# Power_Distribution.net
KiCad netlist of a schematic drawn in EAGLE
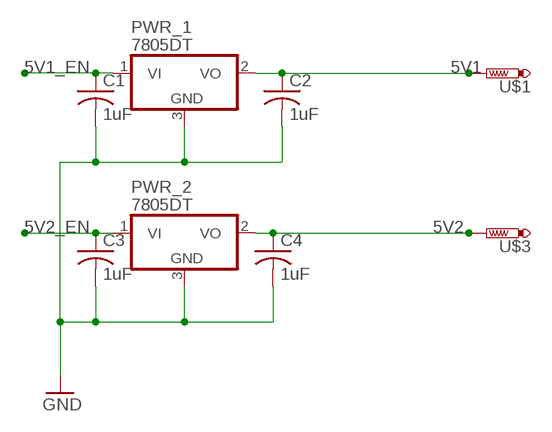
[diagram p0: schematic, sheet 1]
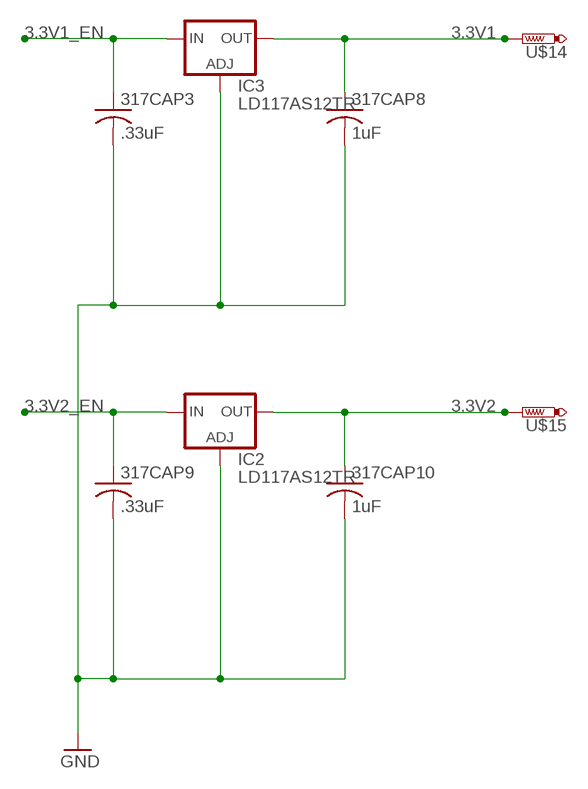
[diagram p1: schematic, sheet 2]
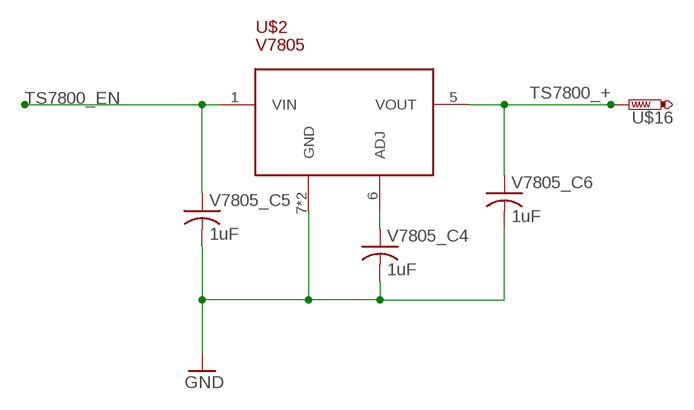
[diagram p2: schematic, sheet 3]
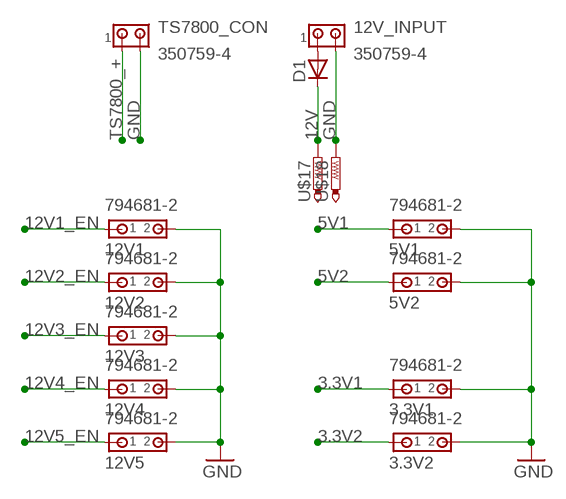
[diagram p3: schematic, sheet 4]
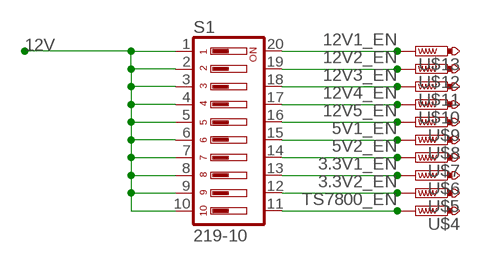
[diagram p4: schematic, sheet 5]

(export (version "E")
  (design (tool "Eeschema 10.0.6"))
  (components
    (comp (ref "S1")
      (value "219-10")
      (footprint "eagle-import:CTS-219-10")
      (fields (field (name "MF") "SLI (CML/IDI)") (field (name "MPN") "219-10PK"))
      (libsource (lib "eagle-import") (part "219-10"))
    )
    (comp (ref "U$4")
      (value "TESTPAD-20MIL")
      (footprint "eagle-import:20MIL")
      (libsource (lib "eagle-import") (part "TESTPAD-20MIL"))
    )
    (comp (ref "U$5")
      (value "TESTPAD-20MIL")
      (footprint "eagle-import:20MIL")
      (libsource (lib "eagle-import") (part "TESTPAD-20MIL"))
    )
    (comp (ref "U$6")
      (value "TESTPAD-20MIL")
      (footprint "eagle-import:20MIL")
      (libsource (lib "eagle-import") (part "TESTPAD-20MIL"))
    )
    (comp (ref "U$7")
      (value "TESTPAD-20MIL")
      (footprint "eagle-import:20MIL")
      (libsource (lib "eagle-import") (part "TESTPAD-20MIL"))
    )
    (comp (ref "U$8")
      (value "TESTPAD-20MIL")
      (footprint "eagle-import:20MIL")
      (libsource (lib "eagle-import") (part "TESTPAD-20MIL"))
    )
    (comp (ref "U$9")
      (value "TESTPAD-20MIL")
      (footprint "eagle-import:20MIL")
      (libsource (lib "eagle-import") (part "TESTPAD-20MIL"))
    )
    (comp (ref "U$10")
      (value "TESTPAD-20MIL")
      (footprint "eagle-import:20MIL")
      (libsource (lib "eagle-import") (part "TESTPAD-20MIL"))
    )
    (comp (ref "U$11")
      (value "TESTPAD-20MIL")
      (footprint "eagle-import:20MIL")
      (libsource (lib "eagle-import") (part "TESTPAD-20MIL"))
    )
    (comp (ref "U$12")
      (value "TESTPAD-20MIL")
      (footprint "eagle-import:20MIL")
      (libsource (lib "eagle-import") (part "TESTPAD-20MIL"))
    )
    (comp (ref "U$13")
      (value "TESTPAD-20MIL")
      (footprint "eagle-import:20MIL")
      (libsource (lib "eagle-import") (part "TESTPAD-20MIL"))
    )
    (comp (ref "U$2")
      (value "V7805")
      (footprint "eagle-import:V7805")
      (libsource (lib "eagle-import") (part "V7805"))
    )
    (comp (ref "U$16")
      (value "TESTPAD-20MIL")
      (footprint "eagle-import:20MIL")
      (libsource (lib "eagle-import") (part "TESTPAD-20MIL"))
    )
    (comp (ref "V7805_C4")
      (value "1uF")
      (footprint "eagle-import:C1206")
      (libsource (lib "eagle-import") (part "C-USC1206"))
    )
    (comp (ref "V7805_C5")
      (value "1uF")
      (footprint "eagle-import:C1206")
      (libsource (lib "eagle-import") (part "C-USC1206"))
    )
    (comp (ref "V7805_C6")
      (value "1uF")
      (footprint "eagle-import:C1206")
      (libsource (lib "eagle-import") (part "C-USC1206"))
    )
    (comp (ref "3.3V1")
      (value "794681-2")
      (footprint "eagle-import:794681-2")
      (libsource (lib "eagle-import") (part "794681-2"))
    )
    (comp (ref "3.3V2")
      (value "794681-2")
      (footprint "eagle-import:794681-2")
      (libsource (lib "eagle-import") (part "794681-2"))
    )
    (comp (ref "5V1")
      (value "794681-2")
      (footprint "eagle-import:794681-2")
      (libsource (lib "eagle-import") (part "794681-2"))
    )
    (comp (ref "5V2")
      (value "794681-2")
      (footprint "eagle-import:794681-2")
      (libsource (lib "eagle-import") (part "794681-2"))
    )
    (comp (ref "12V1")
      (value "794681-2")
      (footprint "eagle-import:794681-2")
      (libsource (lib "eagle-import") (part "794681-2"))
    )
    (comp (ref "12V2")
      (value "794681-2")
      (footprint "eagle-import:794681-2")
      (libsource (lib "eagle-import") (part "794681-2"))
    )
    (comp (ref "12V3")
      (value "794681-2")
      (footprint "eagle-import:794681-2")
      (libsource (lib "eagle-import") (part "794681-2"))
    )
    (comp (ref "12V4")
      (value "794681-2")
      (footprint "eagle-import:794681-2")
      (libsource (lib "eagle-import") (part "794681-2"))
    )
    (comp (ref "12V5")
      (value "794681-2")
      (footprint "eagle-import:794681-2")
      (libsource (lib "eagle-import") (part "794681-2"))
    )
    (comp (ref "12V_INPUT")
      (value "350759-4")
      (footprint "eagle-import:350759-4")
      (libsource (lib "eagle-import") (part "350759-4"))
    )
    (comp (ref "D1")
      (value "DIODE-SOD123")
      (footprint "eagle-import:SOD123")
      (libsource (lib "eagle-import") (part "DIODE-SOD123"))
    )
    (comp (ref "TS7800_CON")
      (value "350759-4")
      (footprint "eagle-import:350759-4")
      (libsource (lib "eagle-import") (part "350759-4"))
    )
    (comp (ref "U$17")
      (value "TESTPAD-20MIL")
      (footprint "eagle-import:20MIL")
      (libsource (lib "eagle-import") (part "TESTPAD-20MIL"))
    )
    (comp (ref "U$18")
      (value "TESTPAD-20MIL")
      (footprint "eagle-import:20MIL")
      (libsource (lib "eagle-import") (part "TESTPAD-20MIL"))
    )
    (comp (ref "317CAP3")
      (value ".33uF")
      (footprint "eagle-import:C1206")
      (libsource (lib "eagle-import") (part "C-USC1206"))
    )
    (comp (ref "317CAP8")
      (value "1uF")
      (footprint "eagle-import:C1206")
      (libsource (lib "eagle-import") (part "C-USC1206"))
    )
    (comp (ref "317CAP9")
      (value ".33uF")
      (footprint "eagle-import:C1206")
      (libsource (lib "eagle-import") (part "C-USC1206"))
    )
    (comp (ref "317CAP10")
      (value "1uF")
      (footprint "eagle-import:C1206")
      (libsource (lib "eagle-import") (part "C-USC1206"))
    )
    (comp (ref "IC2")
      (value "LD117AS12TR")
      (footprint "eagle-import:SOT223")
      (libsource (lib "eagle-import") (part "LD117A?S12TR"))
    )
    (comp (ref "IC3")
      (value "LD117AS12TR")
      (footprint "eagle-import:SOT223")
      (libsource (lib "eagle-import") (part "LD117A?S12TR"))
    )
    (comp (ref "U$14")
      (value "TESTPAD-20MIL")
      (footprint "eagle-import:20MIL")
      (libsource (lib "eagle-import") (part "TESTPAD-20MIL"))
    )
    (comp (ref "U$15")
      (value "TESTPAD-20MIL")
      (footprint "eagle-import:20MIL")
      (libsource (lib "eagle-import") (part "TESTPAD-20MIL"))
    )
    (comp (ref "C1")
      (value "1uF")
      (footprint "eagle-import:C1206")
      (libsource (lib "eagle-import") (part "C-USC1206"))
    )
    (comp (ref "C2")
      (value "1uF")
      (footprint "eagle-import:C1206")
      (libsource (lib "eagle-import") (part "C-USC1206"))
    )
    (comp (ref "C3")
      (value "1uF")
      (footprint "eagle-import:C1206")
      (libsource (lib "eagle-import") (part "C-USC1206"))
    )
    (comp (ref "C4")
      (value "1uF")
      (footprint "eagle-import:C1206")
      (libsource (lib "eagle-import") (part "C-USC1206"))
    )
    (comp (ref "PWR_1")
      (value "7805DT")
      (footprint "eagle-import:TO252")
      (libsource (lib "eagle-import") (part "78DT05"))
    )
    (comp (ref "PWR_2")
      (value "7805DT")
      (footprint "eagle-import:TO252")
      (libsource (lib "eagle-import") (part "78DT05"))
    )
    (comp (ref "U$1")
      (value "TESTPAD-20MIL")
      (footprint "eagle-import:20MIL")
      (libsource (lib "eagle-import") (part "TESTPAD-20MIL"))
    )
    (comp (ref "U$3")
      (value "TESTPAD-20MIL")
      (footprint "eagle-import:20MIL")
      (libsource (lib "eagle-import") (part "TESTPAD-20MIL"))
    )
  )
  (nets
    (net (code "1") (name "3.3V1") (class "Default")
      (node (ref "3.3V1") (pin "1") (pinfunction "1_1") (pintype "passive"))
      (node (ref "317CAP8") (pin "1") (pinfunction "1_1") (pintype "passive"))
      (node (ref "IC3") (pin "4") (pinfunction "OUT_4") (pintype "passive"))
      (node (ref "U$14") (pin "P$1") (pinfunction "TP_P$1") (pintype "input"))
    )
    (net (code "2") (name "3.3V1_EN") (class "Default")
      (node (ref "317CAP3") (pin "1") (pinfunction "1_1") (pintype "passive"))
      (node (ref "IC3") (pin "3") (pinfunction "IN_3") (pintype "input"))
      (node (ref "S1") (pin "13") (pinfunction "13_13") (pintype "passive"))
      (node (ref "U$6") (pin "P$1") (pinfunction "TP_P$1") (pintype "input"))
    )
    (net (code "3") (name "3.3V2") (class "Default")
      (node (ref "3.3V2") (pin "1") (pinfunction "1_1") (pintype "passive"))
      (node (ref "317CAP10") (pin "1") (pinfunction "1_1") (pintype "passive"))
      (node (ref "IC2") (pin "4") (pinfunction "OUT_4") (pintype "passive"))
      (node (ref "U$15") (pin "P$1") (pinfunction "TP_P$1") (pintype "input"))
    )
    (net (code "4") (name "3.3V2_EN") (class "Default")
      (node (ref "317CAP9") (pin "1") (pinfunction "1_1") (pintype "passive"))
      (node (ref "IC2") (pin "3") (pinfunction "IN_3") (pintype "input"))
      (node (ref "S1") (pin "12") (pinfunction "12_12") (pintype "passive"))
      (node (ref "U$5") (pin "P$1") (pinfunction "TP_P$1") (pintype "input"))
    )
    (net (code "5") (name "5V1") (class "Default")
      (node (ref "5V1") (pin "1") (pinfunction "1_1") (pintype "passive"))
      (node (ref "C2") (pin "1") (pinfunction "1_1") (pintype "passive"))
      (node (ref "PWR_1") (pin "2") (pinfunction "VO_2") (pintype "passive"))
      (node (ref "U$1") (pin "P$1") (pinfunction "TP_P$1") (pintype "input"))
    )
    (net (code "6") (name "5V1_EN") (class "Default")
      (node (ref "C1") (pin "1") (pinfunction "1_1") (pintype "passive"))
      (node (ref "PWR_1") (pin "1") (pinfunction "VI_1") (pintype "input"))
      (node (ref "S1") (pin "15") (pinfunction "15_15") (pintype "passive"))
      (node (ref "U$8") (pin "P$1") (pinfunction "TP_P$1") (pintype "input"))
    )
    (net (code "7") (name "5V2") (class "Default")
      (node (ref "5V2") (pin "1") (pinfunction "1_1") (pintype "passive"))
      (node (ref "C4") (pin "1") (pinfunction "1_1") (pintype "passive"))
      (node (ref "PWR_2") (pin "2") (pinfunction "VO_2") (pintype "passive"))
      (node (ref "U$3") (pin "P$1") (pinfunction "TP_P$1") (pintype "input"))
    )
    (net (code "8") (name "5V2_EN") (class "Default")
      (node (ref "C3") (pin "1") (pinfunction "1_1") (pintype "passive"))
      (node (ref "PWR_2") (pin "1") (pinfunction "VI_1") (pintype "input"))
      (node (ref "S1") (pin "14") (pinfunction "14_14") (pintype "passive"))
      (node (ref "U$7") (pin "P$1") (pinfunction "TP_P$1") (pintype "input"))
    )
    (net (code "9") (name "12V") (class "Default")
      (node (ref "D1") (pin "C") (pinfunction "C_C") (pintype "passive"))
      (node (ref "S1") (pin "1") (pinfunction "1_1") (pintype "passive"))
      (node (ref "S1") (pin "10") (pinfunction "10_10") (pintype "passive"))
      (node (ref "S1") (pin "2") (pinfunction "2_2") (pintype "passive"))
      (node (ref "S1") (pin "3") (pinfunction "3_3") (pintype "passive"))
      (node (ref "S1") (pin "4") (pinfunction "4_4") (pintype "passive"))
      (node (ref "S1") (pin "5") (pinfunction "5_5") (pintype "passive"))
      (node (ref "S1") (pin "6") (pinfunction "6_6") (pintype "passive"))
      (node (ref "S1") (pin "7") (pinfunction "7_7") (pintype "passive"))
      (node (ref "S1") (pin "8") (pinfunction "8_8") (pintype "passive"))
      (node (ref "S1") (pin "9") (pinfunction "9_9") (pintype "passive"))
      (node (ref "U$17") (pin "P$1") (pinfunction "TP_P$1") (pintype "input"))
    )
    (net (code "10") (name "12V1_EN") (class "Default")
      (node (ref "12V1") (pin "1") (pinfunction "1_1") (pintype "passive"))
      (node (ref "S1") (pin "20") (pinfunction "20_20") (pintype "passive"))
      (node (ref "U$13") (pin "P$1") (pinfunction "TP_P$1") (pintype "input"))
    )
    (net (code "11") (name "12V2_EN") (class "Default")
      (node (ref "12V2") (pin "1") (pinfunction "1_1") (pintype "passive"))
      (node (ref "S1") (pin "19") (pinfunction "19_19") (pintype "passive"))
      (node (ref "U$12") (pin "P$1") (pinfunction "TP_P$1") (pintype "input"))
    )
    (net (code "12") (name "12V3_EN") (class "Default")
      (node (ref "12V3") (pin "1") (pinfunction "1_1") (pintype "passive"))
      (node (ref "S1") (pin "18") (pinfunction "18_18") (pintype "passive"))
      (node (ref "U$11") (pin "P$1") (pinfunction "TP_P$1") (pintype "input"))
    )
    (net (code "13") (name "12V4_EN") (class "Default")
      (node (ref "12V4") (pin "1") (pinfunction "1_1") (pintype "passive"))
      (node (ref "S1") (pin "17") (pinfunction "17_17") (pintype "passive"))
      (node (ref "U$10") (pin "P$1") (pinfunction "TP_P$1") (pintype "input"))
    )
    (net (code "14") (name "12V5_EN") (class "Default")
      (node (ref "12V5") (pin "1") (pinfunction "1_1") (pintype "passive"))
      (node (ref "S1") (pin "16") (pinfunction "16_16") (pintype "passive"))
      (node (ref "U$9") (pin "P$1") (pinfunction "TP_P$1") (pintype "input"))
    )
    (net (code "15") (name "GND") (class "Default")
      (node (ref "12V1") (pin "2") (pinfunction "2_2") (pintype "passive"))
      (node (ref "12V2") (pin "2") (pinfunction "2_2") (pintype "passive"))
      (node (ref "12V3") (pin "2") (pinfunction "2_2") (pintype "passive"))
      (node (ref "12V4") (pin "2") (pinfunction "2_2") (pintype "passive"))
      (node (ref "12V5") (pin "2") (pinfunction "2_2") (pintype "passive"))
      (node (ref "12V_INPUT") (pin "2") (pinfunction "2_2") (pintype "passive"))
      (node (ref "3.3V1") (pin "2") (pinfunction "2_2") (pintype "passive"))
      (node (ref "3.3V2") (pin "2") (pinfunction "2_2") (pintype "passive"))
      (node (ref "317CAP10") (pin "2") (pinfunction "2_2") (pintype "passive"))
      (node (ref "317CAP3") (pin "2") (pinfunction "2_2") (pintype "passive"))
      (node (ref "317CAP8") (pin "2") (pinfunction "2_2") (pintype "passive"))
      (node (ref "317CAP9") (pin "2") (pinfunction "2_2") (pintype "passive"))
      (node (ref "5V1") (pin "2") (pinfunction "2_2") (pintype "passive"))
      (node (ref "5V2") (pin "2") (pinfunction "2_2") (pintype "passive"))
      (node (ref "C1") (pin "2") (pinfunction "2_2") (pintype "passive"))
      (node (ref "C2") (pin "2") (pinfunction "2_2") (pintype "passive"))
      (node (ref "C3") (pin "2") (pinfunction "2_2") (pintype "passive"))
      (node (ref "C4") (pin "2") (pinfunction "2_2") (pintype "passive"))
      (node (ref "IC2") (pin "1") (pinfunction "ADJ_1") (pintype "input"))
      (node (ref "IC3") (pin "1") (pinfunction "ADJ_1") (pintype "input"))
      (node (ref "PWR_1") (pin "3") (pinfunction "GND_3") (pintype "passive"))
      (node (ref "PWR_2") (pin "3") (pinfunction "GND_3") (pintype "passive"))
      (node (ref "TS7800_CON") (pin "2") (pinfunction "2_2") (pintype "passive"))
      (node (ref "U$18") (pin "P$1") (pinfunction "TP_P$1") (pintype "input"))
      (node (ref "U$2") (pin "7") (pinfunction "GND_7") (pintype "bidirectional"))
      (node (ref "U$2") (pin "9") (pinfunction "GND_9") (pintype "bidirectional"))
      (node (ref "V7805_C4") (pin "2") (pinfunction "2_2") (pintype "passive"))
      (node (ref "V7805_C5") (pin "2") (pinfunction "2_2") (pintype "passive"))
      (node (ref "V7805_C6") (pin "2") (pinfunction "2_2") (pintype "passive"))
    )
    (net (code "16") (name "Net-(12V_INPUT-Pad1)") (class "Default")
      (node (ref "12V_INPUT") (pin "1") (pinfunction "1_1") (pintype "passive"))
      (node (ref "D1") (pin "A") (pinfunction "A_A") (pintype "passive"))
    )
    (net (code "17") (name "Net-(U$2-ADJ)") (class "Default")
      (node (ref "U$2") (pin "6") (pinfunction "ADJ_6") (pintype "bidirectional"))
      (node (ref "V7805_C4") (pin "1") (pinfunction "1_1") (pintype "passive"))
    )
    (net (code "18") (name "TS7800_+") (class "Default")
      (node (ref "TS7800_CON") (pin "1") (pinfunction "1_1") (pintype "passive"))
      (node (ref "U$16") (pin "P$1") (pinfunction "TP_P$1") (pintype "input"))
      (node (ref "U$2") (pin "5") (pinfunction "VOUT_5") (pintype "bidirectional"))
      (node (ref "V7805_C6") (pin "1") (pinfunction "1_1") (pintype "passive"))
    )
    (net (code "19") (name "TS7800_EN") (class "Default")
      (node (ref "S1") (pin "11") (pinfunction "11_11") (pintype "passive"))
      (node (ref "U$2") (pin "1") (pinfunction "VIN_1") (pintype "bidirectional"))
      (node (ref "U$4") (pin "P$1") (pinfunction "TP_P$1") (pintype "input"))
      (node (ref "V7805_C5") (pin "1") (pinfunction "1_1") (pintype "passive"))
    )
  )
)
